# dongle.net
KiCad netlist of a schematic drawn in Altium Designer
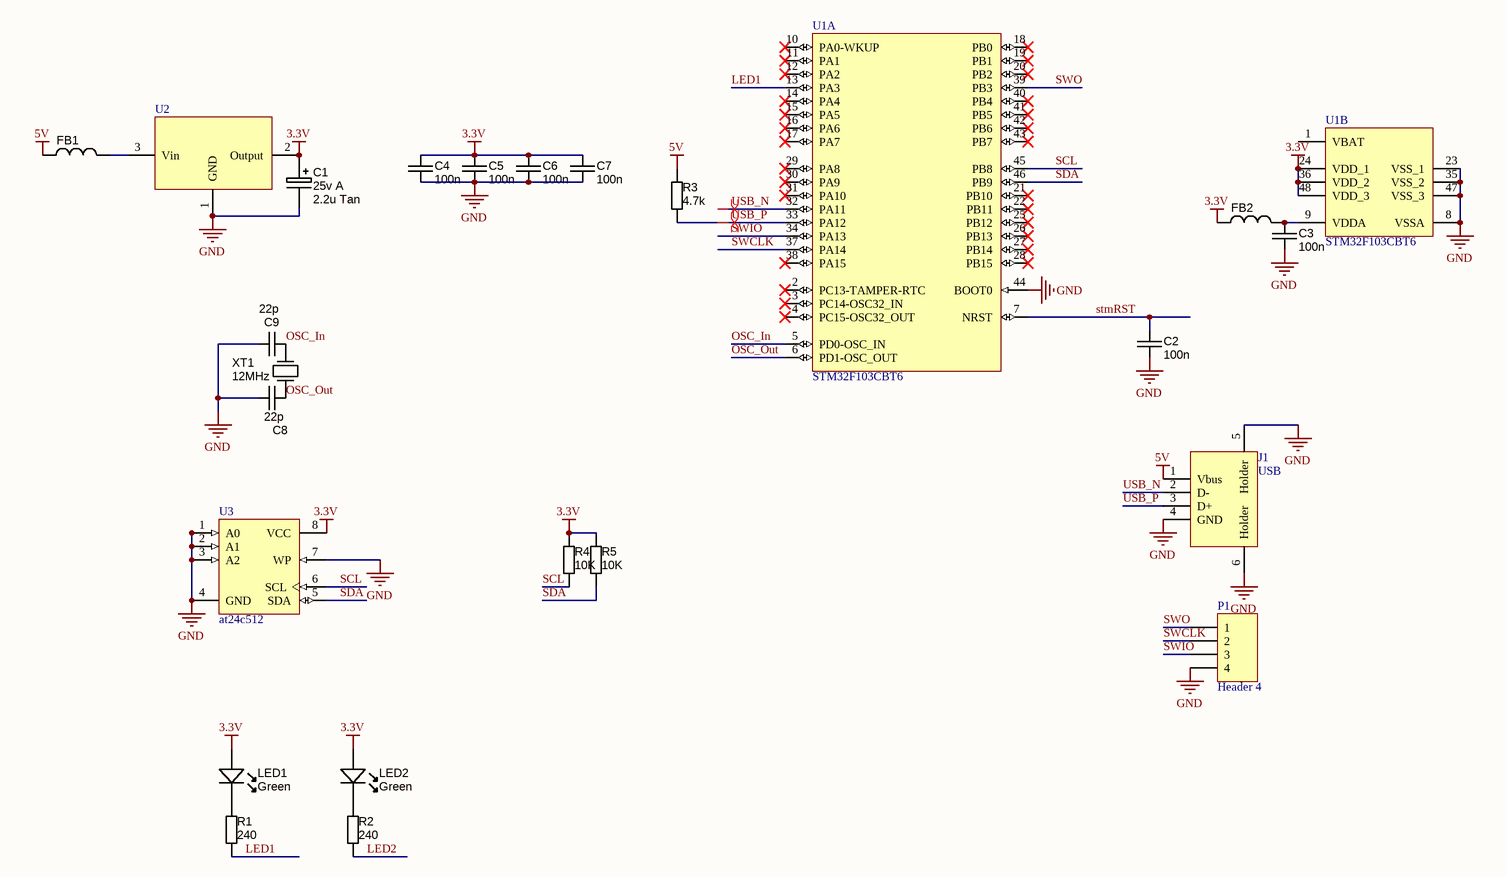
[diagram p0: dongle.SchDoc]

(export (version "E")
  (design (tool "Eeschema 10.0.6"))
  (components
    (comp (ref "C1")
      (value "2.2u Tan")
      (footprint "CAPMP3528X210N")
      (description "Capacitor SMD Tantalum 47uF 20% 6.3V 1210")
      (fields (field (name "TOLERANCE") "±20%") (field (name "RATINGS") "25v A"))
      (libsource (lib "PBL - Capacitors") (part "CAPT_47u_1210_6V3"))
    )
    (comp (ref "C2")
      (value "100n")
      (footprint "CAPC1608X90N")
      (description "Capacitor SMD Cer 1nF 10% 100V X7R 0603")
      (fields (field (name "TOLERANCE") "±10%") (field (name "Comment") "approved sub OK"))
      (libsource (lib "PBL - Capacitors") (part "CAPC_1n_0603_X7R_100V_10%"))
    )
    (comp (ref "C3")
      (value "100n")
      (footprint "CAPC1608X90N")
      (description "Capacitor SMD Cer 1nF 10% 100V X7R 0603")
      (fields (field (name "TOLERANCE") "±10%") (field (name "Comment") "approved sub OK"))
      (libsource (lib "PBL - Capacitors") (part "CAPC_1n_0603_X7R_100V_10%"))
    )
    (comp (ref "C4")
      (value "100n")
      (footprint "CAPC1608X90N")
      (description "Capacitor SMD Cer 1nF 10% 100V X7R 0603")
      (fields (field (name "TOLERANCE") "±10%") (field (name "Comment") "approved sub OK"))
      (libsource (lib "PBL - Capacitors") (part "CAPC_1n_0603_X7R_100V_10%"))
    )
    (comp (ref "C5")
      (value "100n")
      (footprint "CAPC1608X90N")
      (description "Capacitor SMD Cer 1nF 10% 100V X7R 0603")
      (fields (field (name "TOLERANCE") "±10%") (field (name "Comment") "approved sub OK"))
      (libsource (lib "PBL - Capacitors") (part "CAPC_1n_0603_X7R_100V_10%"))
    )
    (comp (ref "C6")
      (value "100n")
      (footprint "CAPC1608X90N")
      (description "Capacitor SMD Cer 1nF 10% 100V X7R 0603")
      (fields (field (name "TOLERANCE") "±10%") (field (name "Comment") "approved sub OK"))
      (libsource (lib "PBL - Capacitors") (part "CAPC_1n_0603_X7R_100V_10%"))
    )
    (comp (ref "C7")
      (value "100n")
      (footprint "CAPC1608X90N")
      (description "Capacitor SMD Cer 1nF 10% 100V X7R 0603")
      (fields (field (name "TOLERANCE") "±10%") (field (name "Comment") "approved sub OK"))
      (libsource (lib "PBL - Capacitors") (part "CAPC_1n_0603_X7R_100V_10%"))
    )
    (comp (ref "C8")
      (value "22p")
      (footprint "CAPC1608X90N")
      (description "Capacitor SMD Cer 18pF 2% 100V NP0 0603")
      (fields (field (name "TOLERANCE") "±2%"))
      (libsource (lib "PBL - Capacitors") (part "CAPC_18p_0603_100V"))
    )
    (comp (ref "C9")
      (value "22p")
      (footprint "CAPC1608X90N")
      (description "Capacitor SMD Cer 18pF 2% 100V NP0 0603")
      (fields (field (name "TOLERANCE") "±2%"))
      (libsource (lib "PBL - Capacitors") (part "CAPC_18p_0603_100V"))
    )
    (comp (ref "FB1")
      (value "2K2 @ 100 MHz")
      (footprint "FBC1608X95N")
      (description "Ferrite bead 2.2K Ohm at 100 MHz 200mA 0603 SMD")
      (libsource (lib "PBL - Inductors") (part "FERRITE_2K2-100MHz_0603"))
    )
    (comp (ref "FB2")
      (value "2K2 @ 100 MHz")
      (footprint "FBC1608X95N")
      (description "Ferrite bead 2.2K Ohm at 100 MHz 200mA 0603 SMD")
      (libsource (lib "PBL - Inductors") (part "FERRITE_2K2-100MHz_0603"))
    )
    (comp (ref "J1") (value "USB") (footprint "USB_A_PLUG") (libsource (lib "USB") (part "USB")))
    (comp (ref "LED1")
      (value "~")
      (footprint "LED-0805-K")
      (description "LED, 0805 SMD, Green")
      (fields (field (name "COLOR") "Green"))
      (libsource (lib "PBL - Light Sources") (part "LED_SMD_Green_0805_6mcd"))
    )
    (comp (ref "LED2")
      (value "~")
      (footprint "LED-0805-K")
      (description "LED, 0805 SMD, Green")
      (fields (field (name "COLOR") "Green"))
      (libsource (lib "PBL - Light Sources") (part "LED_SMD_Green_0805_6mcd"))
    )
    (comp (ref "P1")
      (value "Header 4")
      (footprint "HDR1X4")
      (description "Header, 4-Pin")
      (fields (field (name "PUBLISHER") "Altium Limited"))
      (libsource (lib "Miscellaneous Connectors") (part "Header 4"))
    )
    (comp (ref "R1")
      (value "240")
      (footprint "RESC1608X55N")
      (description "Resistor SMD chip 1.5k Ohm 0.1W 5% 0603")
      (fields (field (name "TOLERANCE") "±5%") (field (name "Comment") "Thick Film"))
      (libsource (lib "PBL - Resistors") (part "RES_1K5_0603_5%"))
    )
    (comp (ref "R2")
      (value "240")
      (footprint "RESC1608X55N")
      (description "Resistor SMD chip 1.5k Ohm 0.1W 5% 0603")
      (fields (field (name "TOLERANCE") "±5%") (field (name "Comment") "Thick Film"))
      (libsource (lib "PBL - Resistors") (part "RES_1K5_0603_5%"))
    )
    (comp (ref "R3")
      (value "4.7k")
      (footprint "RESC1608X55N")
      (description "Resistor SMD chip 1.5k Ohm 0.1W 5% 0603")
      (fields (field (name "TOLERANCE") "±5%") (field (name "Comment") "Thick Film"))
      (libsource (lib "PBL - Resistors") (part "RES_1K5_0603_5%"))
    )
    (comp (ref "R4")
      (value "10K")
      (footprint "RESC1608X55N")
      (description "Resistor 0603")
      (fields (field (name "TOLERANCE") "±5%"))
      (libsource (lib "PBL - Resistors") (part "RES_2K2_0603_5%"))
    )
    (comp (ref "R5")
      (value "10K")
      (footprint "RESC1608X55N")
      (description "Resistor 0603")
      (fields (field (name "TOLERANCE") "±5%"))
      (libsource (lib "PBL - Resistors") (part "RES_2K2_0603_5%"))
    )
    (comp (ref "U1")
      (value "STM32F103CBT6")
      (footprint "STM-LQFP48_N")
      (libsource (lib "STMicroelectronics STM32 F1") (part "STM32F103CBT6"))
    )
    (comp (ref "U2") (value "AMS1117") (footprint "AMS1117 3.3") (libsource (lib "Mylib") (part "AMS1117")))
    (comp (ref "U3")
      (value "at24c512")
      (footprint "SOIC127P600X175-8AN")
      (libsource (lib "Atmel Serial EEPROM") (part "AT24C01BN-SP25-B"))
    )
    (comp (ref "XT1")
      (value "12MHz")
      (footprint "CRYSTAL_HC49-US-SM")
      (description "Resonator Ceramic 6.00 MHz 30ppm")
      (libsource (lib "PBL - Resonators") (part "Crystal_6MHz_HC49/US"))
    )
  )
  (nets
    (net (code "1") (name "/LED1") (class "Default")
      (node (ref "R1") (pin "2") (pinfunction "2_2") (pintype "passive"))
      (node (ref "U1") (pin "13") (pinfunction "PA3_13") (pintype "bidirectional"))
    )
    (net (code "2") (name "/LED2") (class "Default")
      (node (ref "R2") (pin "2") (pinfunction "2_2") (pintype "passive"))
    )
    (net (code "3") (name "/OSC_In") (class "Default")
      (node (ref "C9") (pin "2") (pintype "passive"))
      (node (ref "U1") (pin "5") (pinfunction "PD0-OSC_IN_5") (pintype "bidirectional"))
      (node (ref "XT1") (pin "2") (pinfunction "OUT_2") (pintype "passive"))
    )
    (net (code "4") (name "/OSC_Out") (class "Default")
      (node (ref "C8") (pin "2") (pintype "passive"))
      (node (ref "U1") (pin "6") (pinfunction "PD1-OSC_OUT_6") (pintype "bidirectional"))
      (node (ref "XT1") (pin "1") (pinfunction "IN_1") (pintype "passive"))
    )
    (net (code "5") (name "/SCL") (class "Default")
      (node (ref "R4") (pin "1") (pinfunction "1_1") (pintype "passive"))
      (node (ref "U1") (pin "45") (pinfunction "PB8_45") (pintype "bidirectional"))
      (node (ref "U3") (pin "6") (pinfunction "SCL_6") (pintype "input"))
    )
    (net (code "6") (name "/SDA") (class "Default")
      (node (ref "R5") (pin "1") (pinfunction "1_1") (pintype "passive"))
      (node (ref "U1") (pin "46") (pinfunction "PB9_46") (pintype "bidirectional"))
      (node (ref "U3") (pin "5") (pinfunction "SDA_5") (pintype "bidirectional"))
    )
    (net (code "7") (name "/SWCLK") (class "Default")
      (node (ref "P1") (pin "2") (pinfunction "2_2") (pintype "passive"))
      (node (ref "U1") (pin "37") (pinfunction "PA14_37") (pintype "bidirectional"))
    )
    (net (code "8") (name "/SWIO") (class "Default")
      (node (ref "P1") (pin "3") (pinfunction "3_3") (pintype "passive"))
      (node (ref "U1") (pin "34") (pinfunction "PA13_34") (pintype "bidirectional"))
    )
    (net (code "9") (name "/SWO") (class "Default")
      (node (ref "P1") (pin "1") (pinfunction "1_1") (pintype "passive"))
      (node (ref "U1") (pin "39") (pinfunction "PB3_39") (pintype "bidirectional"))
    )
    (net (code "10") (name "/USB_N") (class "Default")
      (node (ref "J1") (pin "2") (pinfunction "D-_2") (pintype "passive"))
      (node (ref "U1") (pin "32") (pinfunction "PA11_32") (pintype "bidirectional"))
    )
    (net (code "11") (name "/USB_P") (class "Default")
      (node (ref "J1") (pin "3") (pinfunction "D+_3") (pintype "passive"))
      (node (ref "R3") (pin "2") (pinfunction "2_2") (pintype "passive"))
      (node (ref "U1") (pin "33") (pinfunction "PA12_33") (pintype "bidirectional"))
    )
    (net (code "12") (name "/stmRST") (class "Default")
      (node (ref "C2") (pin "1") (pintype "passive"))
      (node (ref "U1") (pin "7") (pinfunction "NRST_7") (pintype "bidirectional"))
    )
    (net (code "13") (name "3.3V") (class "Default")
      (node (ref "C1") (pin "1") (pintype "passive"))
      (node (ref "C4") (pin "1") (pintype "passive"))
      (node (ref "C5") (pin "1") (pintype "passive"))
      (node (ref "C6") (pin "1") (pintype "passive"))
      (node (ref "C7") (pin "1") (pintype "passive"))
      (node (ref "FB2") (pin "1") (pinfunction "1_1") (pintype "passive"))
      (node (ref "LED1") (pin "A") (pinfunction "A_A") (pintype "passive"))
      (node (ref "LED2") (pin "A") (pinfunction "A_A") (pintype "passive"))
      (node (ref "R4") (pin "2") (pinfunction "2_2") (pintype "passive"))
      (node (ref "R5") (pin "2") (pinfunction "2_2") (pintype "passive"))
      (node (ref "U1") (pin "24") (pinfunction "VDD_1_24") (pintype "power_in"))
      (node (ref "U1") (pin "36") (pinfunction "VDD_2_36") (pintype "power_in"))
      (node (ref "U1") (pin "48") (pinfunction "VDD_3_48") (pintype "power_in"))
      (node (ref "U2") (pin "2") (pinfunction "Output_2") (pintype "passive"))
      (node (ref "U3") (pin "8") (pinfunction "VCC_8") (pintype "power_in"))
    )
    (net (code "14") (name "5V") (class "Default")
      (node (ref "FB1") (pin "1") (pinfunction "1_1") (pintype "passive"))
      (node (ref "J1") (pin "1") (pinfunction "Vbus_1") (pintype "passive"))
      (node (ref "R3") (pin "1") (pinfunction "1_1") (pintype "passive"))
    )
    (net (code "15") (name "GND") (class "Default")
      (node (ref "C1") (pin "2") (pintype "passive"))
      (node (ref "C2") (pin "2") (pintype "passive"))
      (node (ref "C3") (pin "2") (pintype "passive"))
      (node (ref "C4") (pin "2") (pintype "passive"))
      (node (ref "C5") (pin "2") (pintype "passive"))
      (node (ref "C6") (pin "2") (pintype "passive"))
      (node (ref "C7") (pin "2") (pintype "passive"))
      (node (ref "C8") (pin "1") (pintype "passive"))
      (node (ref "C9") (pin "1") (pintype "passive"))
      (node (ref "J1") (pin "4") (pinfunction "GND_4") (pintype "passive"))
      (node (ref "J1") (pin "5") (pinfunction "Holder_5") (pintype "passive"))
      (node (ref "J1") (pin "6") (pinfunction "Holder_6") (pintype "passive"))
      (node (ref "P1") (pin "4") (pinfunction "4_4") (pintype "passive"))
      (node (ref "U1") (pin "23") (pinfunction "VSS_1_23") (pintype "power_in"))
      (node (ref "U1") (pin "35") (pinfunction "VSS_2_35") (pintype "power_in"))
      (node (ref "U1") (pin "44") (pinfunction "BOOT0_44") (pintype "input"))
      (node (ref "U1") (pin "47") (pinfunction "VSS_3_47") (pintype "power_in"))
      (node (ref "U1") (pin "8") (pinfunction "VSSA_8") (pintype "power_in"))
      (node (ref "U2") (pin "1") (pinfunction "GND_1") (pintype "passive"))
      (node (ref "U3") (pin "1") (pinfunction "A0_1") (pintype "input"))
      (node (ref "U3") (pin "2") (pinfunction "A1_2") (pintype "input"))
      (node (ref "U3") (pin "3") (pinfunction "A2_3") (pintype "input"))
      (node (ref "U3") (pin "4") (pinfunction "GND_4") (pintype "power_in"))
      (node (ref "U3") (pin "7") (pinfunction "WP_7") (pintype "input"))
    )
    (net (code "16") (name "Net-(LED1-PadK)") (class "Default")
      (node (ref "LED1") (pin "K") (pinfunction "K_K") (pintype "passive"))
      (node (ref "R1") (pin "1") (pinfunction "1_1") (pintype "passive"))
    )
    (net (code "17") (name "Net-(LED2-PadK)") (class "Default")
      (node (ref "LED2") (pin "K") (pinfunction "K_K") (pintype "passive"))
      (node (ref "R2") (pin "1") (pinfunction "1_1") (pintype "passive"))
    )
    (net (code "18") (name "Net-(U1B-VDDA)") (class "Default")
      (node (ref "C3") (pin "1") (pintype "passive"))
      (node (ref "FB2") (pin "2") (pinfunction "2_2") (pintype "passive"))
      (node (ref "U1") (pin "9") (pinfunction "VDDA_9") (pintype "power_in"))
    )
    (net (code "19") (name "Net-(U2-Vin)") (class "Default")
      (node (ref "FB1") (pin "2") (pinfunction "2_2") (pintype "passive"))
      (node (ref "U2") (pin "3") (pinfunction "Vin_3") (pintype "passive"))
    )
    (net (code "20") (name "unconnected-(U1A-PA0-WKUP-Pad10)") (class "Default")
      (node (ref "U1") (pin "10") (pinfunction "PA0-WKUP_10") (pintype "bidirectional+no_connect"))
    )
    (net (code "21") (name "unconnected-(U1A-PA1-Pad11)") (class "Default")
      (node (ref "U1") (pin "11") (pinfunction "PA1_11") (pintype "bidirectional+no_connect"))
    )
    (net (code "22") (name "unconnected-(U1A-PA2-Pad12)") (class "Default")
      (node (ref "U1") (pin "12") (pinfunction "PA2_12") (pintype "bidirectional+no_connect"))
    )
    (net (code "23") (name "unconnected-(U1A-PA4-Pad14)") (class "Default")
      (node (ref "U1") (pin "14") (pinfunction "PA4_14") (pintype "bidirectional+no_connect"))
    )
    (net (code "24") (name "unconnected-(U1A-PA5-Pad15)") (class "Default")
      (node (ref "U1") (pin "15") (pinfunction "PA5_15") (pintype "bidirectional+no_connect"))
    )
    (net (code "25") (name "unconnected-(U1A-PA6-Pad16)") (class "Default")
      (node (ref "U1") (pin "16") (pinfunction "PA6_16") (pintype "bidirectional+no_connect"))
    )
    (net (code "26") (name "unconnected-(U1A-PA7-Pad17)") (class "Default")
      (node (ref "U1") (pin "17") (pinfunction "PA7_17") (pintype "bidirectional+no_connect"))
    )
    (net (code "27") (name "unconnected-(U1A-PA8-Pad29)") (class "Default")
      (node (ref "U1") (pin "29") (pinfunction "PA8_29") (pintype "bidirectional+no_connect"))
    )
    (net (code "28") (name "unconnected-(U1A-PA9-Pad30)") (class "Default")
      (node (ref "U1") (pin "30") (pinfunction "PA9_30") (pintype "bidirectional+no_connect"))
    )
    (net (code "29") (name "unconnected-(U1A-PA10-Pad31)") (class "Default")
      (node (ref "U1") (pin "31") (pinfunction "PA10_31") (pintype "bidirectional+no_connect"))
    )
    (net (code "30") (name "unconnected-(U1A-PA15-Pad38)") (class "Default")
      (node (ref "U1") (pin "38") (pinfunction "PA15_38") (pintype "bidirectional+no_connect"))
    )
    (net (code "31") (name "unconnected-(U1A-PB0-Pad18)") (class "Default")
      (node (ref "U1") (pin "18") (pinfunction "PB0_18") (pintype "bidirectional+no_connect"))
    )
    (net (code "32") (name "unconnected-(U1A-PB1-Pad19)") (class "Default")
      (node (ref "U1") (pin "19") (pinfunction "PB1_19") (pintype "bidirectional+no_connect"))
    )
    (net (code "33") (name "unconnected-(U1A-PB2-Pad20)") (class "Default")
      (node (ref "U1") (pin "20") (pinfunction "PB2_20") (pintype "bidirectional+no_connect"))
    )
    (net (code "34") (name "unconnected-(U1A-PB4-Pad40)") (class "Default")
      (node (ref "U1") (pin "40") (pinfunction "PB4_40") (pintype "bidirectional+no_connect"))
    )
    (net (code "35") (name "unconnected-(U1A-PB5-Pad41)") (class "Default")
      (node (ref "U1") (pin "41") (pinfunction "PB5_41") (pintype "bidirectional+no_connect"))
    )
    (net (code "36") (name "unconnected-(U1A-PB6-Pad42)") (class "Default")
      (node (ref "U1") (pin "42") (pinfunction "PB6_42") (pintype "bidirectional+no_connect"))
    )
    (net (code "37") (name "unconnected-(U1A-PB7-Pad43)") (class "Default")
      (node (ref "U1") (pin "43") (pinfunction "PB7_43") (pintype "bidirectional+no_connect"))
    )
    (net (code "38") (name "unconnected-(U1A-PB10-Pad21)") (class "Default")
      (node (ref "U1") (pin "21") (pinfunction "PB10_21") (pintype "bidirectional+no_connect"))
    )
    (net (code "39") (name "unconnected-(U1A-PB11-Pad22)") (class "Default")
      (node (ref "U1") (pin "22") (pinfunction "PB11_22") (pintype "bidirectional+no_connect"))
    )
    (net (code "40") (name "unconnected-(U1A-PB12-Pad25)") (class "Default")
      (node (ref "U1") (pin "25") (pinfunction "PB12_25") (pintype "bidirectional+no_connect"))
    )
    (net (code "41") (name "unconnected-(U1A-PB13-Pad26)") (class "Default")
      (node (ref "U1") (pin "26") (pinfunction "PB13_26") (pintype "bidirectional+no_connect"))
    )
    (net (code "42") (name "unconnected-(U1A-PB14-Pad27)") (class "Default")
      (node (ref "U1") (pin "27") (pinfunction "PB14_27") (pintype "bidirectional+no_connect"))
    )
    (net (code "43") (name "unconnected-(U1A-PB15-Pad28)") (class "Default")
      (node (ref "U1") (pin "28") (pinfunction "PB15_28") (pintype "bidirectional+no_connect"))
    )
    (net (code "44") (name "unconnected-(U1A-PC13-TAMPER-RTC-Pad2)") (class "Default")
      (node (ref "U1") (pin "2") (pinfunction "PC13-TAMPER-RTC_2") (pintype "bidirectional+no_connect"))
    )
    (net (code "45") (name "unconnected-(U1A-PC14-OSC32_IN-Pad3)") (class "Default")
      (node (ref "U1") (pin "3") (pinfunction "PC14-OSC32_IN_3") (pintype "bidirectional+no_connect"))
    )
    (net (code "46") (name "unconnected-(U1A-PC15-OSC32_OUT-Pad4)") (class "Default")
      (node (ref "U1") (pin "4") (pinfunction "PC15-OSC32_OUT_4") (pintype "bidirectional+no_connect"))
    )
    (net (code "47") (name "unconnected-(U1B-VBAT-Pad1)") (class "Default")
      (node (ref "U1") (pin "1") (pinfunction "VBAT_1") (pintype "power_in"))
    )
  )
)
